# Fuzz_pbc.net
KiCad netlist of a schematic drawn in EAGLE
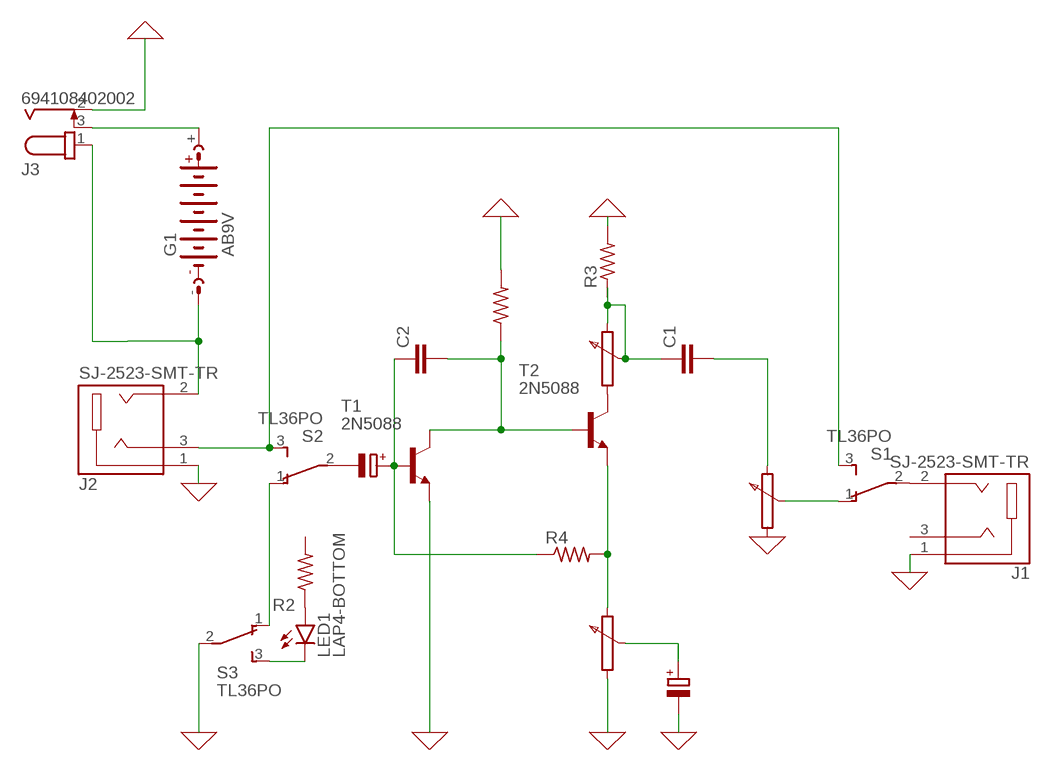
[diagram p0: schematic, sheet 1]

(export (version "E")
  (design (tool "Eeschema 10.0.6"))
  (components
    (comp (ref "C1")
      (value "C2.5/2")
      (footprint "eagle-import:C2.5-2")
      (libsource (lib "eagle-import") (part "C2.5/2"))
    )
    (comp (ref "C2")
      (value "C2.5/2")
      (footprint "eagle-import:C2.5-2")
      (libsource (lib "eagle-import") (part "C2.5/2"))
    )
    (comp (ref "G1")
      (value "AB9V")
      (footprint "eagle-import:AB9V")
      (libsource (lib "eagle-import") (part "AB9V"))
    )
    (comp (ref "J1")
      (value "SJ-2523-SMT-TR")
      (footprint "eagle-import:SJ-2523-SMT-TR")
      (fields (field (name "MANUFACTURER") "CUI Devices") (field (name "CREATED_BY") "PCBLayout.com"))
      (libsource (lib "eagle-import") (part "SJ-2523-SMT-TR"))
    )
    (comp (ref "J2")
      (value "SJ-2523-SMT-TR")
      (footprint "eagle-import:SJ-2523-SMT-TR")
      (fields (field (name "MANUFACTURER") "CUI Devices") (field (name "CREATED_BY") "PCBLayout.com"))
      (libsource (lib "eagle-import") (part "SJ-2523-SMT-TR"))
    )
    (comp (ref "J3")
      (value "694108402002")
      (footprint "eagle-import:694108402002")
      (fields
        (field (name "DIGIKEY_PART_NUMBER") "732-5935-ND")
        (field (name "MANUFACTURER") "Wurth Electronics Inc.")
        (field (name "CREATED_BY") "PCBLayout.com")
      )
      (libsource (lib "eagle-import") (part "694108402002"))
    )
    (comp (ref "LED1")
      (value "LAP4-BOTTOM")
      (footprint "eagle-import:P47F-BOTTOM")
      (libsource (lib "eagle-import") (part "P4-BOTTOMLA"))
    )
    (comp (ref "R1")
      (value "R-US_0204/7")
      (footprint "eagle-import:0204_7")
      (libsource (lib "eagle-import") (part "R-US_0204/7"))
    )
    (comp (ref "R2")
      (value "R-US_0204/7")
      (footprint "eagle-import:0204_7")
      (libsource (lib "eagle-import") (part "R-US_0204/7"))
    )
    (comp (ref "R3")
      (value "R-US_0204/7")
      (footprint "eagle-import:0204_7")
      (libsource (lib "eagle-import") (part "R-US_0204/7"))
    )
    (comp (ref "R4")
      (value "R-US_0204/7")
      (footprint "eagle-import:0204_7")
      (libsource (lib "eagle-import") (part "R-US_0204/7"))
    )
    (comp (ref "S1")
      (value "TL36PO")
      (footprint "eagle-import:TL3XPO")
      (libsource (lib "eagle-import") (part "TL36PO"))
    )
    (comp (ref "S2")
      (value "TL36PO")
      (footprint "eagle-import:TL3XPO")
      (libsource (lib "eagle-import") (part "TL36PO"))
    )
    (comp (ref "S3")
      (value "TL36PO")
      (footprint "eagle-import:TL3XPO")
      (libsource (lib "eagle-import") (part "TL36PO"))
    )
    (comp (ref "T1")
      (value "2N5088")
      (footprint "eagle-import:TO92")
      (libsource (lib "eagle-import") (part "2N5088"))
    )
    (comp (ref "T2")
      (value "2N5088")
      (footprint "eagle-import:TO92")
      (libsource (lib "eagle-import") (part "2N5088"))
    )
  )
  (nets
    (net (code "1") (name "GND") (class "Default")
      (node (ref "J1") (pin "1") (pinfunction "SLEEVE_1") (pintype "passive"))
      (node (ref "J2") (pin "1") (pinfunction "SLEEVE_1") (pintype "passive"))
      (node (ref "J3") (pin "2") (pinfunction "2_2") (pintype "passive"))
      (node (ref "R1") (pin "2") (pinfunction "2_2") (pintype "passive"))
      (node (ref "R3") (pin "2") (pinfunction "2_2") (pintype "passive"))
      (node (ref "S3") (pin "2") (pinfunction "P_2") (pintype "passive"))
      (node (ref "T1") (pin "3") (pinfunction "E_3") (pintype "passive"))
    )
    (net (code "2") (name "Net-(G1-Pad+)") (class "Default")
      (node (ref "G1") (pin "+") (pinfunction "+_+") (pintype "passive"))
      (node (ref "J3") (pin "3") (pinfunction "3_3") (pintype "passive"))
    )
    (net (code "3") (name "Net-(J1-TIP)") (class "Default")
      (node (ref "J1") (pin "2") (pinfunction "TIP_2") (pintype "passive"))
      (node (ref "S1") (pin "2") (pinfunction "P_2") (pintype "passive"))
    )
    (net (code "4") (name "Net-(J2-RING)") (class "Default")
      (node (ref "J2") (pin "3") (pinfunction "RING_3") (pintype "passive"))
      (node (ref "S1") (pin "3") (pinfunction "S_3") (pintype "passive"))
      (node (ref "S2") (pin "3") (pinfunction "S_3") (pintype "passive"))
    )
    (net (code "5") (name "Net-(J2-TIP)") (class "Default")
      (node (ref "G1") (pin "-") (pinfunction "-_-") (pintype "passive"))
      (node (ref "J2") (pin "2") (pinfunction "TIP_2") (pintype "passive"))
      (node (ref "J3") (pin "1") (pinfunction "1_1") (pintype "passive"))
    )
    (net (code "6") (name "Net-(LED1-PadA)") (class "Default")
      (node (ref "LED1") (pin "A") (pinfunction "A_A") (pintype "passive"))
      (node (ref "R2") (pin "1") (pinfunction "1_1") (pintype "passive"))
    )
    (net (code "7") (name "Net-(S2-O)") (class "Default")
      (node (ref "S2") (pin "1") (pinfunction "O_1") (pintype "passive"))
      (node (ref "S3") (pin "1") (pinfunction "O_1") (pintype "passive"))
    )
    (net (code "8") (name "Net-(S3-S)") (class "Default")
      (node (ref "LED1") (pin "C") (pinfunction "C_C") (pintype "passive"))
      (node (ref "S3") (pin "3") (pinfunction "S_3") (pintype "passive"))
    )
    (net (code "9") (name "Net-(T1-B)") (class "Default")
      (node (ref "C2") (pin "1") (pinfunction "1_1") (pintype "passive"))
      (node (ref "R4") (pin "1") (pinfunction "1_1") (pintype "passive"))
      (node (ref "T1") (pin "2") (pinfunction "B_2") (pintype "passive"))
    )
    (net (code "10") (name "Net-(T1-C)") (class "Default")
      (node (ref "C2") (pin "2") (pinfunction "2_2") (pintype "passive"))
      (node (ref "R1") (pin "1") (pinfunction "1_1") (pintype "passive"))
      (node (ref "T1") (pin "1") (pinfunction "C_1") (pintype "passive"))
      (node (ref "T2") (pin "2") (pinfunction "B_2") (pintype "passive"))
    )
    (net (code "11") (name "Net-(T2-E)") (class "Default")
      (node (ref "R4") (pin "2") (pinfunction "2_2") (pintype "passive"))
      (node (ref "T2") (pin "3") (pinfunction "E_3") (pintype "passive"))
    )
    (net (code "12") (name "unconnected-(C1-Pad1)") (class "Default")
      (node (ref "C1") (pin "1") (pinfunction "1_1") (pintype "passive"))
    )
    (net (code "13") (name "unconnected-(C1-Pad2)") (class "Default")
      (node (ref "C1") (pin "2") (pinfunction "2_2") (pintype "passive"))
    )
    (net (code "14") (name "unconnected-(J1-RING-Pad3)") (class "Default")
      (node (ref "J1") (pin "3") (pinfunction "RING_3") (pintype "passive"))
    )
    (net (code "15") (name "unconnected-(R2-Pad2)") (class "Default")
      (node (ref "R2") (pin "2") (pinfunction "2_2") (pintype "passive"))
    )
    (net (code "16") (name "unconnected-(R3-Pad1)") (class "Default")
      (node (ref "R3") (pin "1") (pinfunction "1_1") (pintype "passive"))
    )
    (net (code "17") (name "unconnected-(S1-O-Pad1)") (class "Default")
      (node (ref "S1") (pin "1") (pinfunction "O_1") (pintype "passive"))
    )
    (net (code "18") (name "unconnected-(S2-P-Pad2)") (class "Default")
      (node (ref "S2") (pin "2") (pinfunction "P_2") (pintype "passive"))
    )
    (net (code "19") (name "unconnected-(T2-C-Pad1)") (class "Default")
      (node (ref "T2") (pin "1") (pinfunction "C_1") (pintype "passive"))
    )
  )
)
